# RP2350_CNC_board.net
KiCad netlist of a schematic drawn in Altium Designer
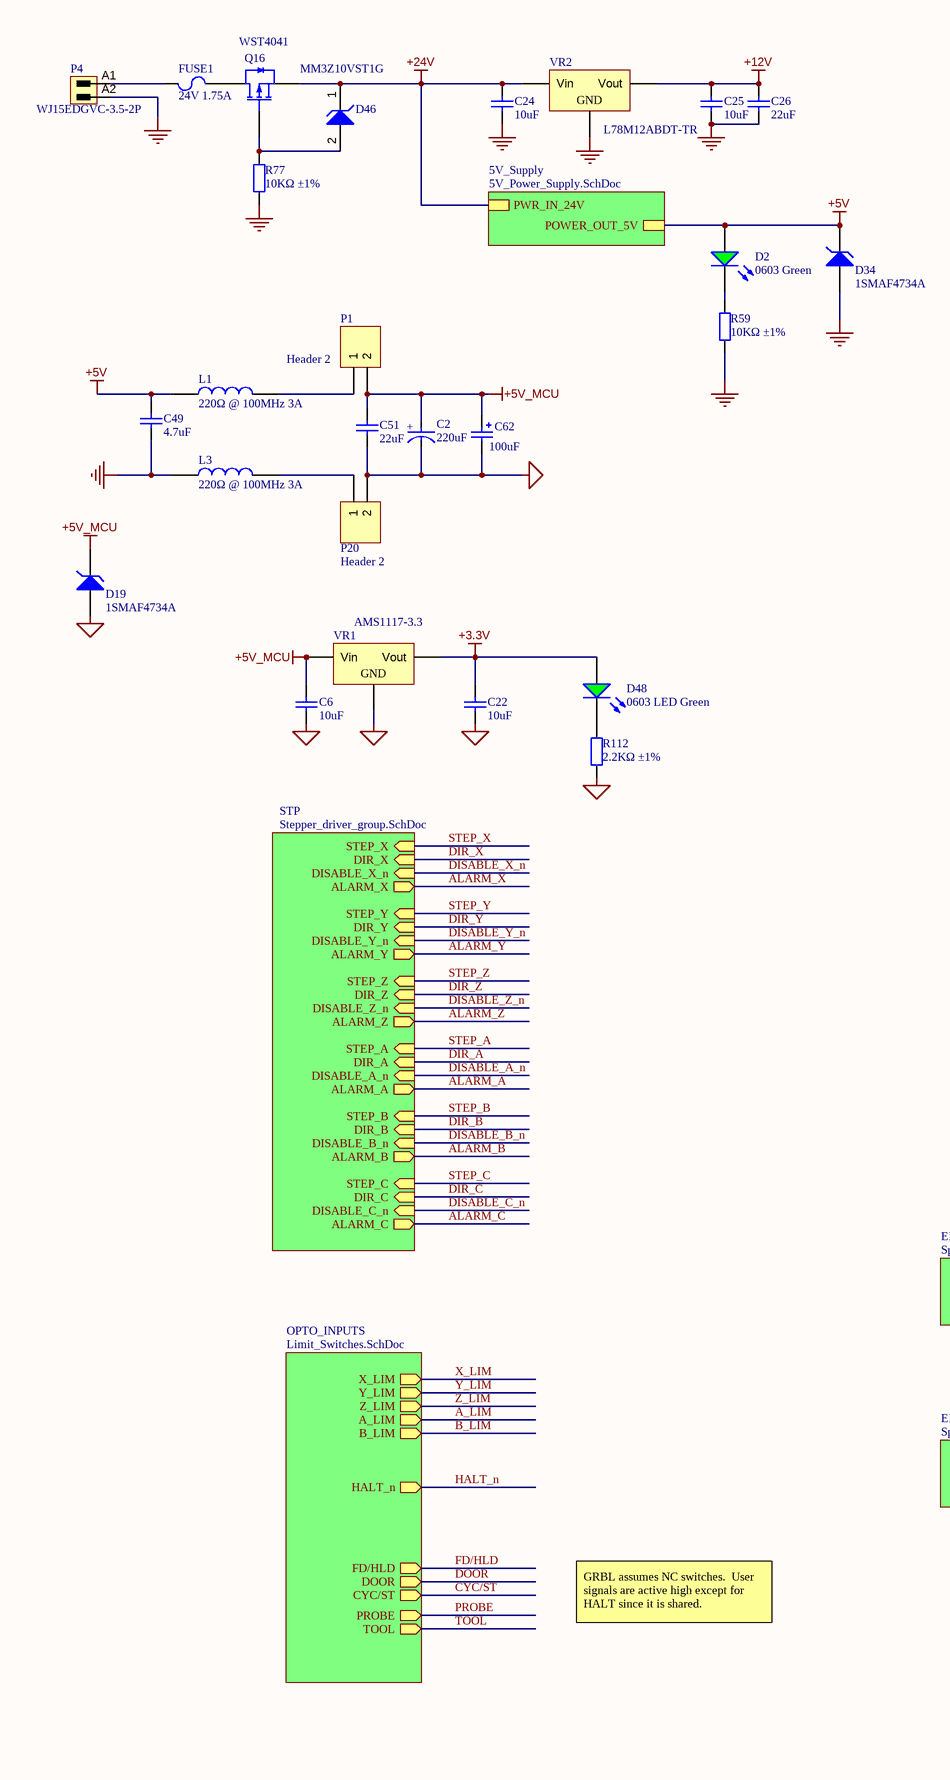
[diagram p0: RP2350_CNC_board.SchDoc, left]
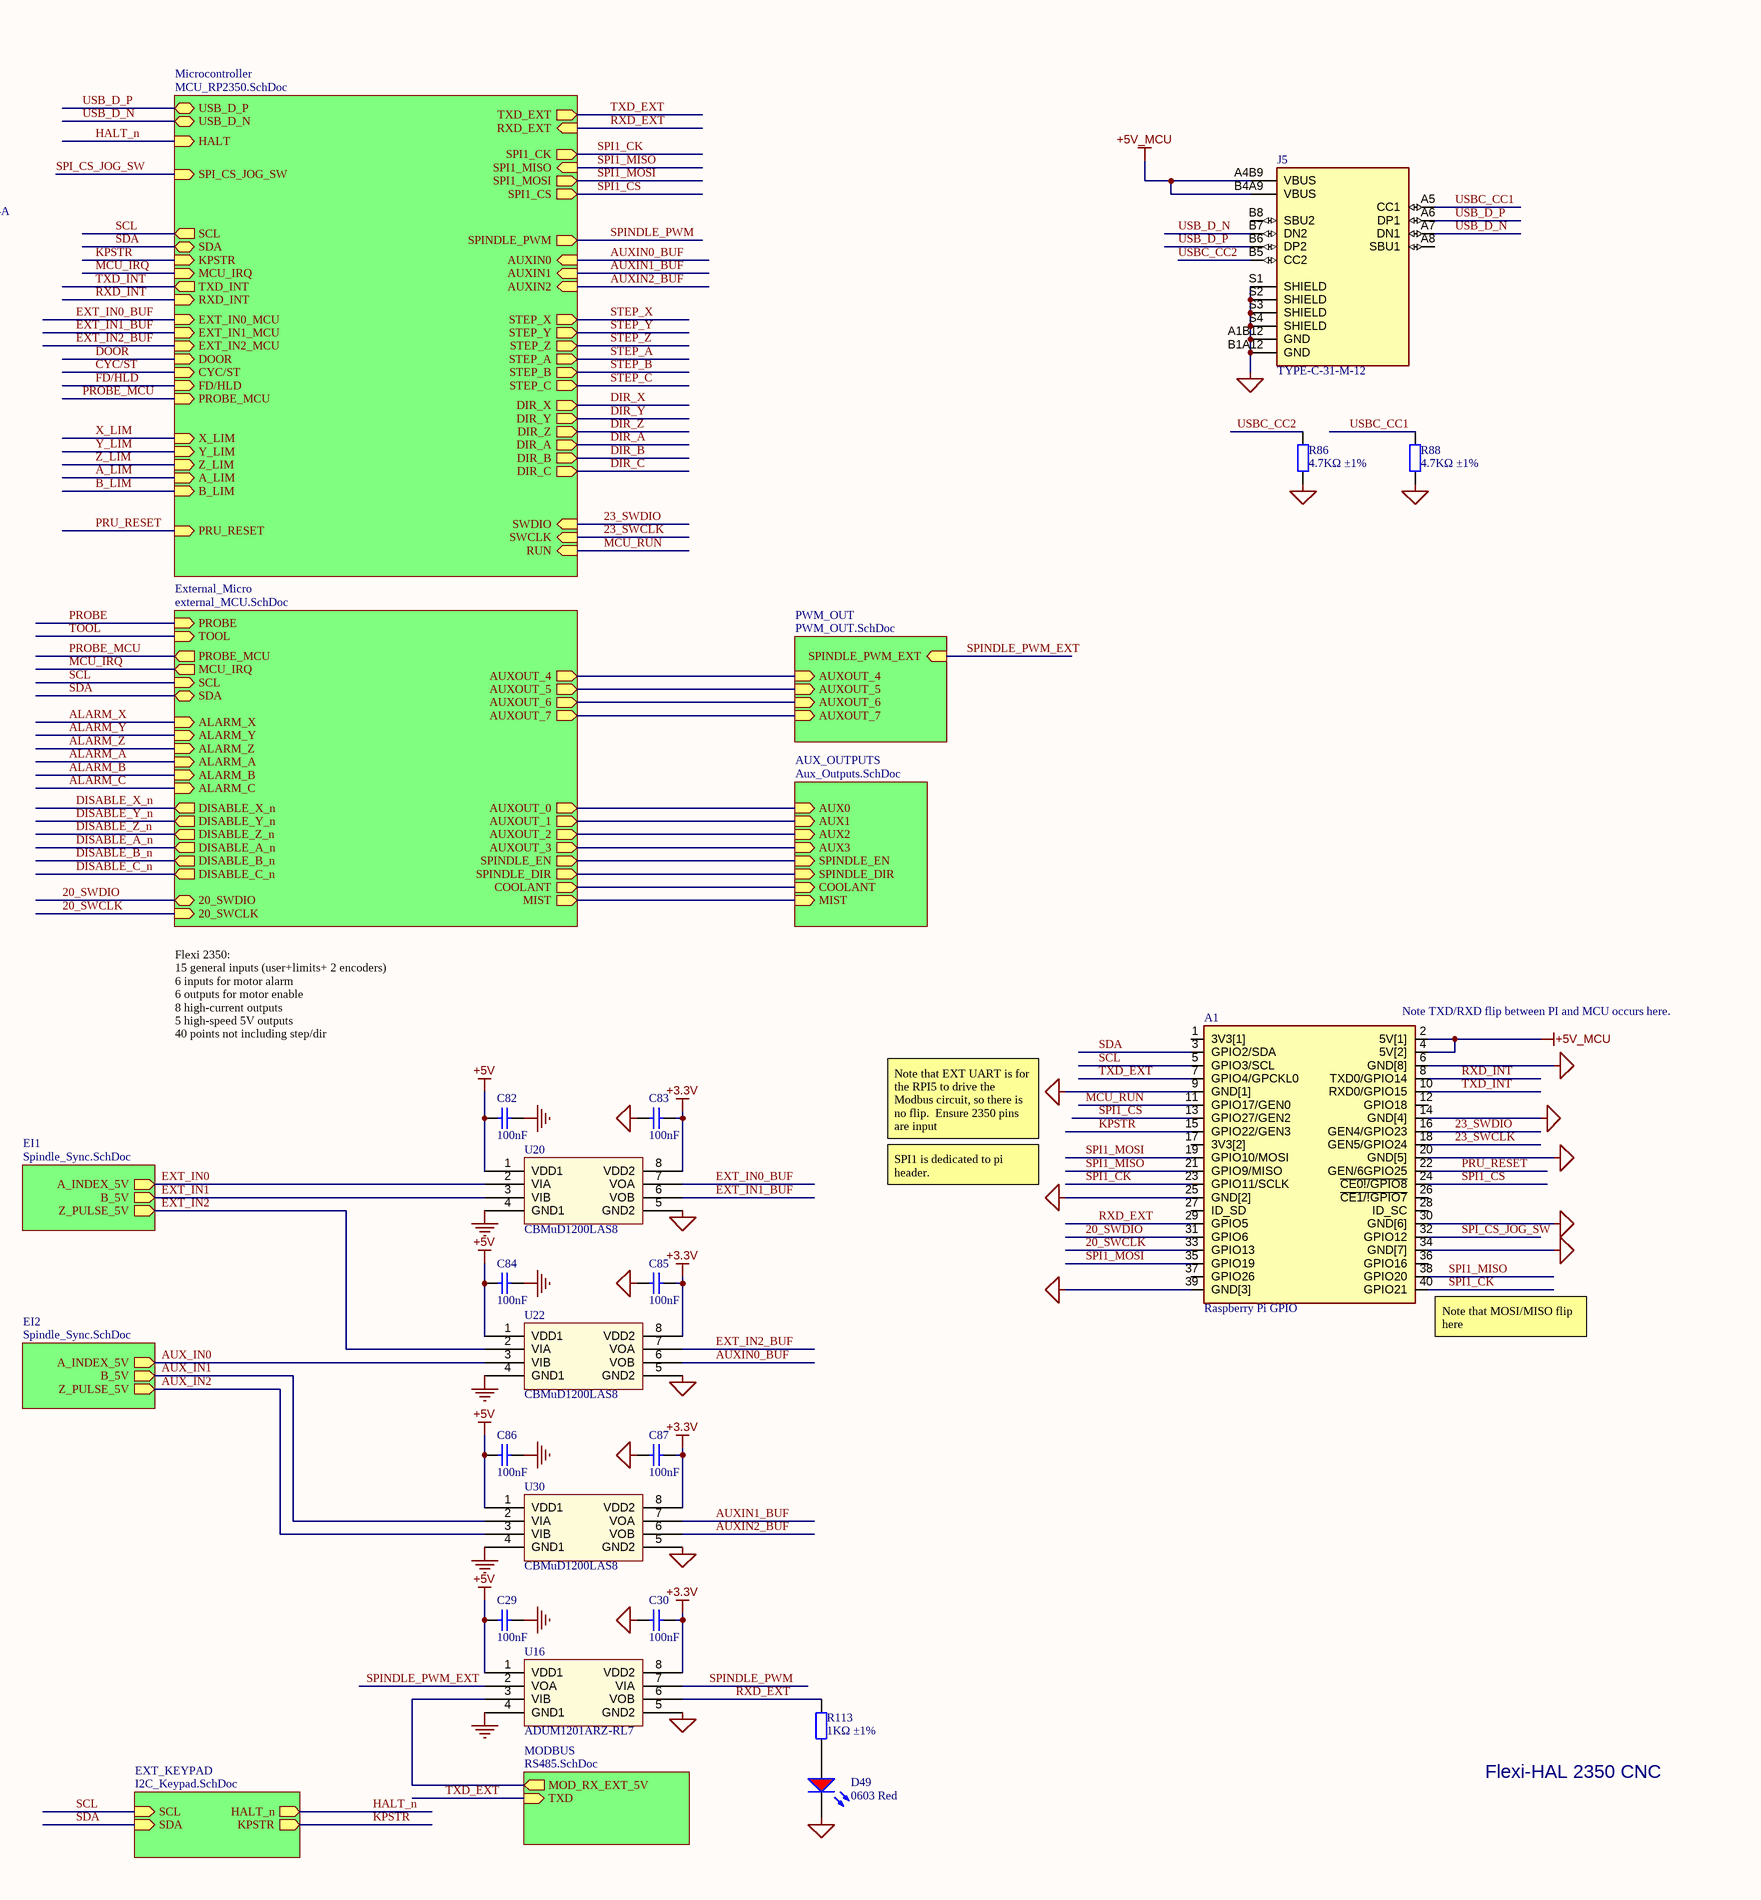
[diagram p1: RP2350_CNC_board.SchDoc, right]

(export (version "E")
  (design (tool "Eeschema 10.0.6"))
  (components
    (comp (ref "A1")
      (value "Raspberry Pi GPIO")
      (footprint "MODULE_RASPBERRY_PI_4_MODEL_B")
      (description "Raspberry Pi Zero WH _Zero W with Headers_")
      (fields (field (name "MP") "DS1023-2*20SF11") (field (name "MF") "CONNFLY Elec"))
      (libsource (lib "Universal_CNC_Breakout") (part "ADA3708"))
    )
    (comp (ref "C2")
      (value "UUD1H221MNL1GS")
      (footprint "FP-FKG-MFG")
      (description "CAP ALUM 220UF 20% 50V SMD")
      (fields
        (field (name "TOLERANCE") "20%")
        (field (name "CAPACITANCE") "220uF")
        (field (name "MANUFACTURER") "Nichicon")
        (field (name "SOURCE") "Sienci_Labs.SchLib")
      )
      (libsource (lib "Cambridge Mobile Telematics, Inc") (part "UUD1H221MNL1GS"))
    )
    (comp (ref "C6")
      (value "10uF")
      (footprint "1206_C")
      (description "Chip capacitors")
      (fields
        (field (name "MANUFACTURER") "Samsung Electro-Mechanics")
        (field (name "PARTNUMBER") "CL31A106KBHNNNE")
      )
      (libsource (lib "Cap") (part "1206 10uF (106) 10% 50V"))
    )
    (comp (ref "C22")
      (value "10uF")
      (footprint "1206_C")
      (description "Chip capacitors")
      (fields
        (field (name "MANUFACTURER") "Samsung Electro-Mechanics")
        (field (name "PARTNUMBER") "CL31A106KBHNNNE")
      )
      (libsource (lib "Cap") (part "1206 10uF (106) 10% 50V"))
    )
    (comp (ref "C24")
      (value "10uF")
      (footprint "1206_C")
      (description "Chip capacitors")
      (fields
        (field (name "MANUFACTURER") "Samsung Electro-Mechanics")
        (field (name "PARTNUMBER") "CL31A106KBHNNNE")
      )
      (libsource (lib "Cap") (part "1206 10uF (106) 10% 50V"))
    )
    (comp (ref "C25")
      (value "10uF")
      (footprint "1206_C")
      (description "Chip capacitors")
      (fields
        (field (name "MANUFACTURER") "Samsung Electro-Mechanics")
        (field (name "PARTNUMBER") "CL31A106KBHNNNE")
      )
      (libsource (lib "Cap") (part "1206 10uF (106) 10% 50V"))
    )
    (comp (ref "C26")
      (value "22uF")
      (footprint "0805_C")
      (description "Chip capacitors")
      (fields
        (field (name "MANUFACTURER") "Samsung Electro-Mechanics")
        (field (name "PARTNUMBER") "CL21A226MAQNNNE")
      )
      (libsource (lib "Cap") (part "0805 22uF (226) 20% 25V"))
    )
    (comp (ref "C29")
      (value "100nF")
      (footprint "0402_C")
      (description "Chip capacitors")
      (fields
        (field (name "MANUFACTURER") "Samsung Electro-Mechanics")
        (field (name "PARTNUMBER") "CL05B104KO5NNNC")
      )
      (libsource (lib "Cap") (part "0402 100nF (104) 10% 16V"))
    )
    (comp (ref "C30")
      (value "100nF")
      (footprint "0402_C")
      (description "Chip capacitors")
      (fields
        (field (name "MANUFACTURER") "Samsung Electro-Mechanics")
        (field (name "PARTNUMBER") "CL05B104KO5NNNC")
      )
      (libsource (lib "Cap") (part "0402 100nF (104) 10% 16V"))
    )
    (comp (ref "C49")
      (value "4.7uF")
      (footprint "0603_C")
      (description "Chip capacitors")
      (fields
        (field (name "MANUFACTURER") "Samsung Electro-Mechanics")
        (field (name "PARTNUMBER") "CL10A475KO8NNNC")
      )
      (libsource (lib "Cap") (part "0603 4.7uF (475) 10% 16V"))
    )
    (comp (ref "C51")
      (value "22uF")
      (footprint "0805_C")
      (description "Chip capacitors")
      (fields
        (field (name "MANUFACTURER") "Samsung Electro-Mechanics")
        (field (name "PARTNUMBER") "CL21A226MAQNNNE")
      )
      (libsource (lib "Cap") (part "0805 22uF (226) 20% 25V"))
    )
    (comp (ref "C62")
      (value "100uF")
      (footprint "WCAP-ASLI_D6.3H7.7")
      (fields (field (name "MANUFACTURER") "Capxon International Elec"))
      (libsource (lib "IQAnalog") (part "865080445010"))
    )
    (comp (ref "C82")
      (value "100nF")
      (footprint "0402_C")
      (description "Chip capacitors")
      (fields
        (field (name "MANUFACTURER") "Samsung Electro-Mechanics")
        (field (name "PARTNUMBER") "CL05B104KO5NNNC")
      )
      (libsource (lib "Cap") (part "0402 100nF (104) 10% 16V"))
    )
    (comp (ref "C83")
      (value "100nF")
      (footprint "0402_C")
      (description "Chip capacitors")
      (fields
        (field (name "MANUFACTURER") "Samsung Electro-Mechanics")
        (field (name "PARTNUMBER") "CL05B104KO5NNNC")
      )
      (libsource (lib "Cap") (part "0402 100nF (104) 10% 16V"))
    )
    (comp (ref "C84")
      (value "100nF")
      (footprint "0402_C")
      (description "Chip capacitors")
      (fields
        (field (name "MANUFACTURER") "Samsung Electro-Mechanics")
        (field (name "PARTNUMBER") "CL05B104KO5NNNC")
      )
      (libsource (lib "Cap") (part "0402 100nF (104) 10% 16V"))
    )
    (comp (ref "C85")
      (value "100nF")
      (footprint "0402_C")
      (description "Chip capacitors")
      (fields
        (field (name "MANUFACTURER") "Samsung Electro-Mechanics")
        (field (name "PARTNUMBER") "CL05B104KO5NNNC")
      )
      (libsource (lib "Cap") (part "0402 100nF (104) 10% 16V"))
    )
    (comp (ref "C86")
      (value "100nF")
      (footprint "0402_C")
      (description "Chip capacitors")
      (fields
        (field (name "MANUFACTURER") "Samsung Electro-Mechanics")
        (field (name "PARTNUMBER") "CL05B104KO5NNNC")
      )
      (libsource (lib "Cap") (part "0402 100nF (104) 10% 16V"))
    )
    (comp (ref "C87")
      (value "100nF")
      (footprint "0402_C")
      (description "Chip capacitors")
      (fields
        (field (name "MANUFACTURER") "Samsung Electro-Mechanics")
        (field (name "PARTNUMBER") "CL05B104KO5NNNC")
      )
      (libsource (lib "Cap") (part "0402 100nF (104) 10% 16V"))
    )
    (comp (ref "D2")
      (value "0603 Green")
      (footprint "0603_LED_S1")
      (description "LED")
      (libsource (lib "LED") (part "0603 LED Green"))
    )
    (comp (ref "D19")
      (value "1SMAF4734A")
      (footprint "DIOM5226X240N")
      (description "27V ±5% 1W 500nA @ 20.5V SMA(DO-214AC) Zener Diodes RoHS")
      (libsource (lib "PrintNC_GRBLHAL_Breakout") (part "BZT52C27"))
    )
    (comp (ref "D34")
      (value "1SMAF4734A")
      (footprint "DIOM5226X240N")
      (description "27V ±5% 1W 500nA @ 20.5V SMA(DO-214AC) Zener Diodes RoHS")
      (libsource (lib "PrintNC_GRBLHAL_Breakout") (part "BZT52C27"))
    )
    (comp (ref "D46")
      (value "MM3Z10VST1G")
      (footprint "ONSC-SOD-323-2-477-02_V")
      (description "MM3Z10VST1G Zener Diode, 10V 2% 300 mW SMT 2-Pin SOD-323 ¦ ON Semiconductor MM3Z10VST1G")
      (fields (field (name "MANUFACTURER") "On Semiconductor") (field (name "TOLERANCE") "2%"))
      (libsource (lib "Sienci_Labs") (part "MM3Z10VST1G"))
    )
    (comp (ref "D48")
      (value "0603 LED Green")
      (footprint "0603_LED_S1 - GREEN")
      (fields
        (field (name "MANUFACTURER PART NUMBER") "19-217/GHC-YR1S2/3T")
        (field (name "MANUFACTURER") "Everlight Elec")
      )
      (libsource (lib "Sienci_Labs") (part "19-217/GHC-YR1S2/3T"))
    )
    (comp (ref "D49")
      (value "0603 Red")
      (footprint "0603_LED_S1")
      (description "LED")
      (libsource (lib "LED") (part "0603 LED Red"))
    )
    (comp (ref "FUSE1")
      (value "24V 1.75A")
      (footprint "1206_C")
      (description "24V 1.75A 0.1s 1206 PTC Resettable Fuses RoHS")
      (libsource (lib "PrintNC_GRBLHAL_Breakout") (part "JK-nSMD050-24"))
    )
    (comp (ref "J5")
      (value "TYPE-C-31-M-12")
      (footprint "HRO_TYPE-C-31-M-12")
      (description "USB Connectors 24 Receptacle 1 8.94*7.3mm RoHS")
      (fields (field (name "MF") "HRO Electronics Co., Ltd."))
      (libsource (lib "Universal_CNC_Breakout") (part "TYPE-C-31-M-12"))
    )
    (comp (ref "L1")
      (value "220Ω @ 100MHz 3A")
      (footprint "0805_C")
      (description "40mΩ ±25% 220Ω@100MHz 0805 Ferrite Beads ROHS")
      (libsource (lib "FBEAD") (part "0402 220R@100Mhz 0.1A"))
    )
    (comp (ref "L3")
      (value "220Ω @ 100MHz 3A")
      (footprint "0805_C")
      (description "40mΩ ±25% 220Ω@100MHz 0805 Ferrite Beads ROHS")
      (libsource (lib "FBEAD") (part "0402 220R@100Mhz 0.1A"))
    )
    (comp (ref "P1")
      (value "Header 2")
      (footprint "HDR1X2")
      (description "Header, 2-Pin")
      (fields (field (name "PUBLISHER") "Altium Limited"))
      (libsource (lib "") (part "Header 2_1"))
    )
    (comp (ref "P4")
      (value "WJ15EDGVC-3.5-2P")
      (footprint "691321100002")
      (libsource (lib "Universal_CNC_Breakout") (part "3.5mm Terminal Header 2p"))
    )
    (comp (ref "P20")
      (value "Header 2")
      (footprint "HDR1X2")
      (description "Header, 2-Pin")
      (fields (field (name "PUBLISHER") "Altium Limited"))
      (libsource (lib "Miscellaneous Connectors") (part "Header 2"))
    )
    (comp (ref "Q16")
      (value "WST4041")
      (footprint "SOT-23-3L")
      (description "40V 6A 40mΩ@10V,3A 1.4W 2.2V 1 piece P-channel SOT-23 MOSFETs ROHS")
      (libsource (lib "MOS") (part "AO3401A P道沟 X13A15 SOT-23"))
    )
    (comp (ref "R59")
      (value "10KΩ ±1%")
      (footprint "0402_R")
      (description "Chip resistor")
      (fields (field (name "MANUFACTURER") "Uniroyal Elec") (field (name "PARTNUMBER") "0402WGF1002TCE"))
      (libsource (lib "RES") (part "0402 10K (1002) 1%"))
    )
    (comp (ref "R77")
      (value "10KΩ ±1%")
      (footprint "0603_R")
      (description "Chip resistor")
      (fields (field (name "MANUFACTURER") "Uniroyal Elec") (field (name "POWER") "1/10W"))
      (libsource (lib "Sienci_Labs") (part "0603 10K (1002) 1%"))
    )
    (comp (ref "R86")
      (value "4.7KΩ ±1%")
      (footprint "0402_R")
      (description "Chip resistor")
      (fields (field (name "MANUFACTURER") "Uniroyal Elec") (field (name "PARTNUMBER") "0402WGF4701TCE"))
      (libsource (lib "RES") (part "0402 4.7K (4701) 1%"))
    )
    (comp (ref "R88")
      (value "4.7KΩ ±1%")
      (footprint "0402_R")
      (description "Chip resistor")
      (fields (field (name "MANUFACTURER") "Uniroyal Elec") (field (name "PARTNUMBER") "0402WGF4701TCE"))
      (libsource (lib "RES") (part "0402 4.7K (4701) 1%"))
    )
    (comp (ref "R112")
      (value "2.2KΩ ±1%")
      (footprint "0402_R")
      (description "Chip resistor")
      (fields (field (name "MANUFACTURER") "Uniroyal Elec") (field (name "POWER") "1/16W"))
      (libsource (lib "RES") (part "0402 2.2K (2201) 1%"))
    )
    (comp (ref "R113")
      (value "1KΩ ±1%")
      (footprint "0402_R")
      (description "Chip resistor")
      (fields (field (name "MANUFACTURER") "Uniroyal Elec") (field (name "PARTNUMBER") "0402WGF1001TCE"))
      (libsource (lib "RES") (part "0402 1K (1001) 1%"))
    )
    (comp (ref "U16")
      (value "ADUM1201ARZ-RL7")
      (footprint "SOIC-8_150mil")
      (description "Dual Channel Isolator")
      (libsource (lib "IC") (part "ADUM1201ARZ-RL7_[C9669]"))
    )
    (comp (ref "U20")
      (value "CBMuD1200LAS8")
      (footprint "SOIC-8_150mil")
      (description "Dual Channel Isolator")
      (libsource (lib "IC") (part "CBMuD1200LAS8"))
    )
    (comp (ref "U22")
      (value "CBMuD1200LAS8")
      (footprint "SOIC-8_150mil")
      (description "Dual Channel Isolator")
      (libsource (lib "IC") (part "CBMuD1200LAS8"))
    )
    (comp (ref "U30")
      (value "CBMuD1200LAS8")
      (footprint "SOIC-8_150mil")
      (description "Dual Channel Isolator")
      (libsource (lib "IC") (part "CBMuD1200LAS8"))
    )
    (comp (ref "VR1")
      (value "AMS1117-3.3")
      (footprint "SOT-223")
      (description "Vout=3.3V 1A 72dB@(120Hz) (LDO)")
      (libsource (lib "LDO") (part "SOT-223 AMS1117-3.3"))
    )
    (comp (ref "VR2")
      (value "L78M12ABDT-TR")
      (footprint "TO-252-2-180")
      (libsource (lib "PrintNC_GRBLHAL_Breakout") (part "TO-252-2 L78M05ABDT-TR"))
    )
  )
  (nets
    (net (code "1") (name "+3.3V") (class "Default")
      (node (ref "C22") (pin "2") (pinfunction "2_2") (pintype "passive"))
      (node (ref "C30") (pin "2") (pinfunction "2_2") (pintype "passive"))
      (node (ref "C83") (pin "2") (pinfunction "2_2") (pintype "passive"))
      (node (ref "C85") (pin "2") (pinfunction "2_2") (pintype "passive"))
      (node (ref "C87") (pin "2") (pinfunction "2_2") (pintype "passive"))
      (node (ref "D48") (pin "A") (pinfunction "A_A") (pintype "passive"))
      (node (ref "U16") (pin "8") (pinfunction "VDD2_8") (pintype "passive"))
      (node (ref "U20") (pin "8") (pinfunction "VDD2_8") (pintype "passive"))
      (node (ref "U22") (pin "8") (pinfunction "VDD2_8") (pintype "passive"))
      (node (ref "U30") (pin "8") (pinfunction "VDD2_8") (pintype "passive"))
      (node (ref "VR1") (pin "2") (pinfunction "Vout_2") (pintype "passive"))
    )
    (net (code "2") (name "+5V") (class "Default")
      (node (ref "C29") (pin "1") (pinfunction "1_1") (pintype "passive"))
      (node (ref "C49") (pin "2") (pinfunction "2_2") (pintype "passive"))
      (node (ref "C82") (pin "1") (pinfunction "1_1") (pintype "passive"))
      (node (ref "C84") (pin "1") (pinfunction "1_1") (pintype "passive"))
      (node (ref "C86") (pin "1") (pinfunction "1_1") (pintype "passive"))
      (node (ref "D2") (pin "A") (pinfunction "A_A") (pintype "passive"))
      (node (ref "D34") (pin "2") (pinfunction "K_2") (pintype "passive"))
      (node (ref "L1") (pin "1") (pinfunction "1_1") (pintype "passive"))
      (node (ref "U16") (pin "1") (pinfunction "VDD1_1") (pintype "passive"))
      (node (ref "U20") (pin "1") (pinfunction "VDD1_1") (pintype "passive"))
      (node (ref "U22") (pin "1") (pinfunction "VDD1_1") (pintype "passive"))
      (node (ref "U30") (pin "1") (pinfunction "VDD1_1") (pintype "passive"))
    )
    (net (code "3") (name "+5V_MCU") (class "Default")
      (node (ref "A1") (pin "2") (pinfunction "5V[1]_2") (pintype "power_in"))
      (node (ref "A1") (pin "4") (pinfunction "5V[2]_4") (pintype "power_in"))
      (node (ref "C2") (pin "2") (pinfunction "A_2") (pintype "passive"))
      (node (ref "C51") (pin "2") (pinfunction "2_2") (pintype "passive"))
      (node (ref "C6") (pin "2") (pinfunction "2_2") (pintype "passive"))
      (node (ref "C62") (pin "1") (pinfunction "P_1") (pintype "passive"))
      (node (ref "D19") (pin "2") (pinfunction "K_2") (pintype "passive"))
      (node (ref "J5") (pin "A4B9") (pinfunction "VBUS_A4B9") (pintype "power_in"))
      (node (ref "J5") (pin "B4A9") (pinfunction "VBUS_B4A9") (pintype "power_in"))
      (node (ref "P1") (pin "2") (pinfunction "2_2") (pintype "passive"))
      (node (ref "VR1") (pin "3") (pinfunction "Vin_3") (pintype "passive"))
    )
    (net (code "4") (name "+12V") (class "Default")
      (node (ref "C25") (pin "2") (pinfunction "2_2") (pintype "passive"))
      (node (ref "C26") (pin "2") (pinfunction "2_2") (pintype "passive"))
      (node (ref "VR2") (pin "3") (pinfunction "Vout_3") (pintype "passive"))
    )
    (net (code "5") (name "+24V") (class "Default")
      (node (ref "C24") (pin "2") (pinfunction "2_2") (pintype "passive"))
      (node (ref "D46") (pin "1") (pinfunction "K_1") (pintype "passive"))
      (node (ref "Q16") (pin "2") (pinfunction "S_2") (pintype "passive"))
      (node (ref "VR2") (pin "1") (pinfunction "Vin_1") (pintype "passive"))
    )
    (net (code "6") (name "/20_SWCLK") (class "Default")
      (node (ref "A1") (pin "33") (pinfunction "GPIO13_33") (pintype "bidirectional"))
    )
    (net (code "7") (name "/20_SWDIO") (class "Default")
      (node (ref "A1") (pin "31") (pinfunction "GPIO6_31") (pintype "bidirectional"))
    )
    (net (code "8") (name "/23_SWCLK") (class "Default")
      (node (ref "A1") (pin "18") (pinfunction "GEN5/GPIO24_18") (pintype "bidirectional"))
    )
    (net (code "9") (name "/23_SWDIO") (class "Default")
      (node (ref "A1") (pin "16") (pinfunction "GEN4/GPIO23_16") (pintype "bidirectional"))
    )
    (net (code "16") (name "/AUXIN0_BUF") (class "Default")
      (node (ref "U22") (pin "6") (pinfunction "VOB_6") (pintype "passive"))
    )
    (net (code "17") (name "/AUXIN1_BUF") (class "Default")
      (node (ref "U30") (pin "7") (pinfunction "VOA_7") (pintype "passive"))
    )
    (net (code "18") (name "/AUXIN2_BUF") (class "Default")
      (node (ref "U30") (pin "6") (pinfunction "VOB_6") (pintype "passive"))
    )
    (net (code "27") (name "/AUX_IN0") (class "Default")
      (node (ref "U22") (pin "3") (pinfunction "VIB_3") (pintype "passive"))
    )
    (net (code "28") (name "/AUX_IN1") (class "Default")
      (node (ref "U30") (pin "2") (pinfunction "VIA_2") (pintype "passive"))
    )
    (net (code "29") (name "/AUX_IN2") (class "Default")
      (node (ref "U30") (pin "3") (pinfunction "VIB_3") (pintype "passive"))
    )
    (net (code "47") (name "/EXT_IN0") (class "Default")
      (node (ref "U20") (pin "2") (pinfunction "VIA_2") (pintype "passive"))
    )
    (net (code "48") (name "/EXT_IN0_BUF") (class "Default")
      (node (ref "U20") (pin "7") (pinfunction "VOA_7") (pintype "passive"))
    )
    (net (code "49") (name "/EXT_IN1") (class "Default")
      (node (ref "U20") (pin "3") (pinfunction "VIB_3") (pintype "passive"))
    )
    (net (code "50") (name "/EXT_IN1_BUF") (class "Default")
      (node (ref "U20") (pin "6") (pinfunction "VOB_6") (pintype "passive"))
    )
    (net (code "51") (name "/EXT_IN2") (class "Default")
      (node (ref "U22") (pin "2") (pinfunction "VIA_2") (pintype "passive"))
    )
    (net (code "52") (name "/EXT_IN2_BUF") (class "Default")
      (node (ref "U22") (pin "7") (pinfunction "VOA_7") (pintype "passive"))
    )
    (net (code "55") (name "/KPSTR") (class "Default")
      (node (ref "A1") (pin "15") (pinfunction "GPIO22/GEN3_15") (pintype "bidirectional"))
    )
    (net (code "57") (name "/MCU_RUN") (class "Default")
      (node (ref "A1") (pin "11") (pinfunction "GPIO17/GEN0_11") (pintype "bidirectional"))
    )
    (net (code "59") (name "/MOD_RX_EXT_5V") (class "Default")
      (node (ref "U16") (pin "3") (pinfunction "VIB_3") (pintype "passive"))
    )
    (net (code "62") (name "/PRU_RESET") (class "Default")
      (node (ref "A1") (pin "22") (pinfunction "GEN/6GPIO25_22") (pintype "bidirectional"))
    )
    (net (code "63") (name "/RXD_EXT") (class "Default")
      (node (ref "A1") (pin "29") (pinfunction "GPIO5_29") (pintype "bidirectional"))
      (node (ref "R113") (pin "1") (pinfunction "1_1") (pintype "passive"))
      (node (ref "U16") (pin "6") (pinfunction "VOB_6") (pintype "passive"))
    )
    (net (code "64") (name "/RXD_INT") (class "Default")
      (node (ref "A1") (pin "8") (pinfunction "TXD0/GPIO14_8") (pintype "bidirectional"))
    )
    (net (code "65") (name "/SCL") (class "Default")
      (node (ref "A1") (pin "5") (pinfunction "GPIO3/SCL_5") (pintype "bidirectional"))
    )
    (net (code "66") (name "/SDA") (class "Default")
      (node (ref "A1") (pin "3") (pinfunction "GPIO2/SDA_3") (pintype "bidirectional"))
    )
    (net (code "67") (name "/SPI1_CK") (class "Default")
      (node (ref "A1") (pin "23") (pinfunction "GPIO11/SCLK_23") (pintype "bidirectional"))
      (node (ref "A1") (pin "40") (pinfunction "GPIO21_40") (pintype "bidirectional"))
    )
    (net (code "68") (name "/SPI1_CS") (class "Default")
      (node (ref "A1") (pin "13") (pinfunction "GPIO27/GEN2_13") (pintype "bidirectional"))
      (node (ref "A1") (pin "24") (pinfunction "~{CE0!/GPIO8}_24") (pintype "bidirectional"))
    )
    (net (code "69") (name "/SPI1_MISO") (class "Default")
      (node (ref "A1") (pin "21") (pinfunction "GPIO9/MISO_21") (pintype "bidirectional"))
      (node (ref "A1") (pin "38") (pinfunction "GPIO20_38") (pintype "bidirectional"))
    )
    (net (code "70") (name "/SPI1_MOSI") (class "Default")
      (node (ref "A1") (pin "19") (pinfunction "GPIO10/MOSI_19") (pintype "bidirectional"))
      (node (ref "A1") (pin "35") (pinfunction "GPIO19_35") (pintype "bidirectional"))
    )
    (net (code "73") (name "/SPINDLE_PWM") (class "Default")
      (node (ref "U16") (pin "7") (pinfunction "VIA_7") (pintype "passive"))
    )
    (net (code "74") (name "/SPINDLE_PWM_EXT") (class "Default")
      (node (ref "U16") (pin "2") (pinfunction "VOA_2") (pintype "passive"))
    )
    (net (code "75") (name "/SPI_CS_JOG_SW") (class "Default")
      (node (ref "A1") (pin "32") (pinfunction "GPIO12_32") (pintype "bidirectional"))
    )
    (net (code "83") (name "/TXD_EXT") (class "Default")
      (node (ref "A1") (pin "7") (pinfunction "GPIO4/GPCKL0_7") (pintype "bidirectional"))
    )
    (net (code "84") (name "/TXD_INT") (class "Default")
      (node (ref "A1") (pin "10") (pinfunction "RXD0/GPIO15_10") (pintype "bidirectional"))
    )
    (net (code "85") (name "/USBC_CC1") (class "Default")
      (node (ref "J5") (pin "A5") (pinfunction "CC1_A5") (pintype "bidirectional"))
      (node (ref "R88") (pin "1") (pinfunction "1_1") (pintype "passive"))
    )
    (net (code "86") (name "/USBC_CC2") (class "Default")
      (node (ref "J5") (pin "B5") (pinfunction "CC2_B5") (pintype "bidirectional"))
      (node (ref "R86") (pin "1") (pinfunction "1_1") (pintype "passive"))
    )
    (net (code "87") (name "/USB_D_N") (class "Default")
      (node (ref "J5") (pin "A7") (pinfunction "DN1_A7") (pintype "bidirectional"))
      (node (ref "J5") (pin "B7") (pinfunction "DN2_B7") (pintype "bidirectional"))
    )
    (net (code "88") (name "/USB_D_P") (class "Default")
      (node (ref "J5") (pin "A6") (pinfunction "DP1_A6") (pintype "bidirectional"))
      (node (ref "J5") (pin "B6") (pinfunction "DP2_B6") (pintype "bidirectional"))
    )
    (net (code "92") (name "GND") (class "Default")
      (node (ref "C24") (pin "1") (pinfunction "1_1") (pintype "passive"))
      (node (ref "C25") (pin "1") (pinfunction "1_1") (pintype "passive"))
      (node (ref "C26") (pin "1") (pinfunction "1_1") (pintype "passive"))
      (node (ref "C29") (pin "2") (pinfunction "2_2") (pintype "passive"))
      (node (ref "C49") (pin "1") (pinfunction "1_1") (pintype "passive"))
      (node (ref "C82") (pin "2") (pinfunction "2_2") (pintype "passive"))
      (node (ref "C84") (pin "2") (pinfunction "2_2") (pintype "passive"))
      (node (ref "C86") (pin "2") (pinfunction "2_2") (pintype "passive"))
      (node (ref "D34") (pin "1") (pinfunction "A_1") (pintype "passive"))
      (node (ref "L3") (pin "1") (pinfunction "1_1") (pintype "passive"))
      (node (ref "P4") (pin "A2") (pinfunction "A2_A2") (pintype "passive"))
      (node (ref "R59") (pin "1") (pinfunction "1_1") (pintype "passive"))
      (node (ref "R77") (pin "1") (pinfunction "1_1") (pintype "passive"))
      (node (ref "U16") (pin "4") (pinfunction "GND1_4") (pintype "passive"))
      (node (ref "U20") (pin "4") (pinfunction "GND1_4") (pintype "passive"))
      (node (ref "U22") (pin "4") (pinfunction "GND1_4") (pintype "passive"))
      (node (ref "U30") (pin "4") (pinfunction "GND1_4") (pintype "passive"))
      (node (ref "VR2") (pin "2") (pinfunction "GND_2") (pintype "passive"))
    )
    (net (code "93") (name "MCU_GND") (class "Default")
      (node (ref "A1") (pin "14") (pinfunction "GND[4]_14") (pintype "power_in"))
      (node (ref "A1") (pin "20") (pinfunction "GND[5]_20") (pintype "power_in"))
      (node (ref "A1") (pin "25") (pinfunction "GND[2]_25") (pintype "power_in"))
      (node (ref "A1") (pin "30") (pinfunction "GND[6]_30") (pintype "power_in"))
      (node (ref "A1") (pin "34") (pinfunction "GND[7]_34") (pintype "power_in"))
      (node (ref "A1") (pin "39") (pinfunction "GND[3]_39") (pintype "power_in"))
      (node (ref "A1") (pin "6") (pinfunction "GND[8]_6") (pintype "power_in"))
      (node (ref "A1") (pin "9") (pinfunction "GND[1]_9") (pintype "power_in"))
      (node (ref "C2") (pin "1") (pinfunction "C_1") (pintype "passive"))
      (node (ref "C22") (pin "1") (pinfunction "1_1") (pintype "passive"))
      (node (ref "C30") (pin "1") (pinfunction "1_1") (pintype "passive"))
      (node (ref "C51") (pin "1") (pinfunction "1_1") (pintype "passive"))
      (node (ref "C6") (pin "1") (pinfunction "1_1") (pintype "passive"))
      (node (ref "C62") (pin "2") (pinfunction "N_2") (pintype "passive"))
      (node (ref "C83") (pin "1") (pinfunction "1_1") (pintype "passive"))
      (node (ref "C85") (pin "1") (pinfunction "1_1") (pintype "passive"))
      (node (ref "C87") (pin "1") (pinfunction "1_1") (pintype "passive"))
      (node (ref "D19") (pin "1") (pinfunction "A_1") (pintype "passive"))
      (node (ref "D49") (pin "K") (pinfunction "K_K") (pintype "passive"))
      (node (ref "J5") (pin "A1B12") (pinfunction "GND_A1B12") (pintype "power_in"))
      (node (ref "J5") (pin "B1A12") (pinfunction "GND_B1A12") (pintype "power_in"))
      (node (ref "J5") (pin "S1") (pinfunction "SHIELD_S1") (pintype "passive"))
      (node (ref "J5") (pin "S2") (pinfunction "SHIELD_S2") (pintype "passive"))
      (node (ref "J5") (pin "S3") (pinfunction "SHIELD_S3") (pintype "passive"))
      (node (ref "J5") (pin "S4") (pinfunction "SHIELD_S4") (pintype "passive"))
      (node (ref "P20") (pin "2") (pinfunction "2_2") (pintype "passive"))
      (node (ref "R112") (pin "1") (pinfunction "1_1") (pintype "passive"))
      (node (ref "R86") (pin "2") (pinfunction "2_2") (pintype "passive"))
      (node (ref "R88") (pin "2") (pinfunction "2_2") (pintype "passive"))
      (node (ref "U16") (pin "5") (pinfunction "GND2_5") (pintype "passive"))
      (node (ref "U20") (pin "5") (pinfunction "GND2_5") (pintype "passive"))
      (node (ref "U22") (pin "5") (pinfunction "GND2_5") (pintype "passive"))
      (node (ref "U30") (pin "5") (pinfunction "GND2_5") (pintype "passive"))
      (node (ref "VR1") (pin "1") (pinfunction "GND_1") (pintype "passive"))
    )
    (net (code "94") (name "Net-(D2-PadK)") (class "Default")
      (node (ref "D2") (pin "K") (pinfunction "K_K") (pintype "passive"))
      (node (ref "R59") (pin "2") (pinfunction "2_2") (pintype "passive"))
    )
    (net (code "95") (name "Net-(D46-A)") (class "Default")
      (node (ref "D46") (pin "2") (pinfunction "A_2") (pintype "passive"))
      (node (ref "Q16") (pin "1") (pinfunction "G_1") (pintype "passive"))
      (node (ref "R77") (pin "2") (pinfunction "2_2") (pintype "passive"))
    )
    (net (code "96") (name "Net-(D48-PadK)") (class "Default")
      (node (ref "D48") (pin "K") (pinfunction "K_K") (pintype "passive"))
      (node (ref "R112") (pin "2") (pinfunction "2_2") (pintype "passive"))
    )
    (net (code "97") (name "Net-(D49-PadA)") (class "Default")
      (node (ref "D49") (pin "A") (pinfunction "A_A") (pintype "passive"))
      (node (ref "R113") (pin "2") (pinfunction "2_2") (pintype "passive"))
    )
    (net (code "98") (name "Net-(FUSE1-Pad1)") (class "Default")
      (node (ref "FUSE1") (pin "1") (pinfunction "1_1") (pintype "passive"))
      (node (ref "P4") (pin "A1") (pinfunction "A1_A1") (pintype "passive"))
    )
    (net (code "99") (name "Net-(L1-Pad2)") (class "Default")
      (node (ref "L1") (pin "2") (pinfunction "2_2") (pintype "passive"))
      (node (ref "P1") (pin "1") (pinfunction "1_1") (pintype "passive"))
    )
    (net (code "100") (name "Net-(L3-Pad2)") (class "Default")
      (node (ref "L3") (pin "2") (pinfunction "2_2") (pintype "passive"))
      (node (ref "P20") (pin "1") (pinfunction "1_1") (pintype "passive"))
    )
    (net (code "101") (name "Net-(Q16-D)") (class "Default")
      (node (ref "FUSE1") (pin "2") (pinfunction "2_2") (pintype "passive"))
      (node (ref "Q16") (pin "3") (pinfunction "D_3") (pintype "passive"))
    )
    (net (code "102") (name "unconnected-(A1-3V3[1]-Pad1)") (class "Default")
      (node (ref "A1") (pin "1") (pinfunction "3V3[1]_1") (pintype "power_in"))
    )
    (net (code "103") (name "unconnected-(A1-3V3[2]-Pad17)") (class "Default")
      (node (ref "A1") (pin "17") (pinfunction "3V3[2]_17") (pintype "power_in"))
    )
    (net (code "104") (name "unconnected-(A1-GPIO16-Pad36)") (class "Default")
      (node (ref "A1") (pin "36") (pinfunction "GPIO16_36") (pintype "bidirectional"))
    )
    (net (code "105") (name "unconnected-(A1-GPIO18-Pad12)") (class "Default")
      (node (ref "A1") (pin "12") (pinfunction "GPIO18_12") (pintype "bidirectional"))
    )
    (net (code "106") (name "unconnected-(A1-GPIO26-Pad37)") (class "Default")
      (node (ref "A1") (pin "37") (pinfunction "GPIO26_37") (pintype "bidirectional"))
    )
    (net (code "107") (name "unconnected-(A1-ID_SC-Pad28)") (class "Default")
      (node (ref "A1") (pin "28") (pinfunction "ID_SC_28") (pintype "bidirectional"))
    )
    (net (code "108") (name "unconnected-(A1-ID_SD-Pad27)") (class "Default")
      (node (ref "A1") (pin "27") (pinfunction "ID_SD_27") (pintype "bidirectional"))
    )
    (net (code "109") (name "unconnected-(A1-~{CE1{slash}!GPIO7}-Pad26)") (class "Default")
      (node (ref "A1") (pin "26") (pinfunction "~{CE1/!GPIO7}_26") (pintype "bidirectional"))
    )
    (net (code "110") (name "unconnected-(J5-SBU1-PadA8)") (class "Default")
      (node (ref "J5") (pin "A8") (pinfunction "SBU1_A8") (pintype "bidirectional"))
    )
    (net (code "111") (name "unconnected-(J5-SBU2-PadB8)") (class "Default")
      (node (ref "J5") (pin "B8") (pinfunction "SBU2_B8") (pintype "bidirectional"))
    )
  )
)
